# wanco_10V_PSUsch.net
KiCad netlist of a schematic drawn in EAGLE
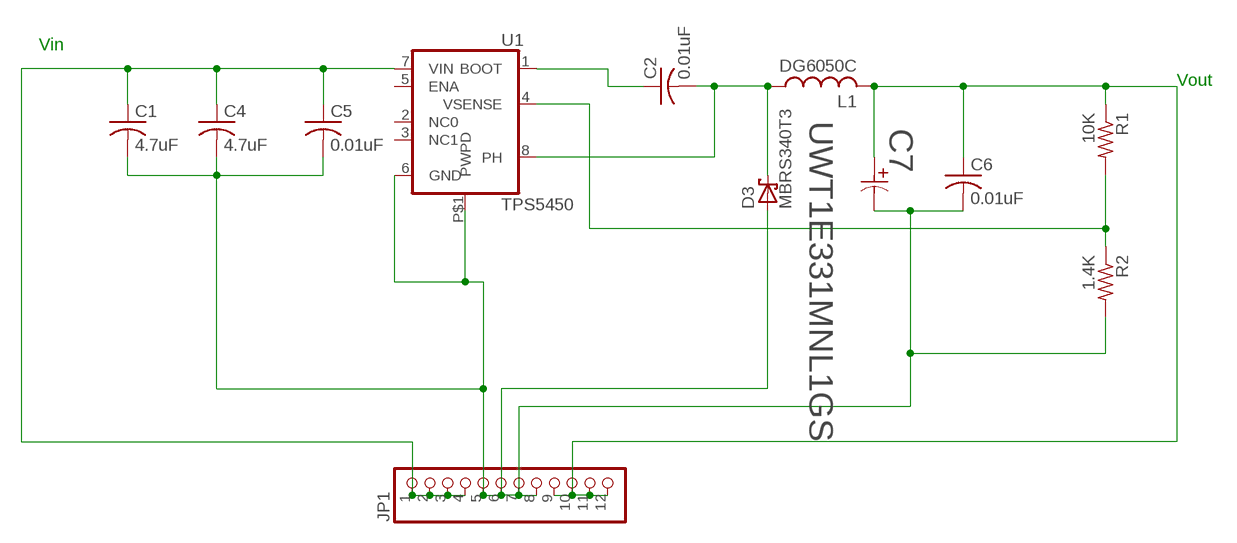
[diagram p0: schematic, sheet 1]

(export (version "E")
  (design (tool "Eeschema 10.0.6"))
  (components
    (comp (ref "C1")
      (value "4.7uF")
      (footprint "eagle-import:C1206")
      (libsource (lib "eagle-import") (part "C-USC1206"))
    )
    (comp (ref "C2")
      (value "0.01uF")
      (footprint "eagle-import:C0805")
      (libsource (lib "eagle-import") (part "resistor_C-USC0805"))
    )
    (comp (ref "C4")
      (value "4.7uF")
      (footprint "eagle-import:C1206")
      (libsource (lib "eagle-import") (part "C-USC1206"))
    )
    (comp (ref "C5")
      (value "0.01uF")
      (footprint "eagle-import:C0805")
      (libsource (lib "eagle-import") (part "resistor_C-USC0805"))
    )
    (comp (ref "C6")
      (value "0.01uF")
      (footprint "eagle-import:C0805")
      (libsource (lib "eagle-import") (part "resistor_C-USC0805"))
    )
    (comp (ref "C7")
      (value "UWT1E331MNL1GS")
      (footprint "eagle-import:PCAP_8X10-ELECT")
      (fields (field (name "COPYRIGHT") "Copyright (C) 2015 Accelerated Designs. All rights reserved"))
      (libsource (lib "eagle-import") (part "UWT1E331MNL1GS"))
    )
    (comp (ref "D3")
      (value "MBRS340T3")
      (footprint "eagle-import:SMC")
      (libsource (lib "eagle-import") (part "MBRS30T34"))
    )
    (comp (ref "JP1")
      (value "PINHD-1X12")
      (footprint "eagle-import:1X12")
      (libsource (lib "eagle-import") (part "PINHD-1X12"))
    )
    (comp (ref "L1")
      (value "DG6050C")
      (footprint "eagle-import:DG")
      (libsource (lib "eagle-import") (part "DG6050C"))
    )
    (comp (ref "R1")
      (value "10K")
      (footprint "eagle-import:R0805")
      (libsource (lib "eagle-import") (part "R-US_R0805"))
    )
    (comp (ref "R2")
      (value "1.4K")
      (footprint "eagle-import:R0805")
      (libsource (lib "eagle-import") (part "R-US_R0805"))
    )
    (comp (ref "U1")
      (value "TPS5450")
      (footprint "eagle-import:SO08")
      (libsource (lib "eagle-import") (part "TPS5450"))
    )
  )
  (nets
    (net (code "1") (name "Net-(C7-11)") (class "Default")
      (node (ref "C6") (pin "1") (pinfunction "1_1") (pintype "passive"))
      (node (ref "C7") (pin "1") (pinfunction "11_1") (pintype "passive"))
      (node (ref "JP1") (pin "10") (pinfunction "10_10") (pintype "passive"))
      (node (ref "JP1") (pin "11") (pinfunction "11_11") (pintype "passive"))
      (node (ref "JP1") (pin "12") (pinfunction "12_12") (pintype "passive"))
      (node (ref "JP1") (pin "9") (pinfunction "9_9") (pintype "passive"))
      (node (ref "L1") (pin "P$2") (pinfunction "2_P$2") (pintype "passive"))
      (node (ref "R1") (pin "1") (pinfunction "1_1") (pintype "passive"))
    )
    (net (code "2") (name "Net-(C7-22)") (class "Default")
      (node (ref "C1") (pin "2") (pinfunction "2_2") (pintype "passive"))
      (node (ref "C4") (pin "2") (pinfunction "2_2") (pintype "passive"))
      (node (ref "C5") (pin "2") (pinfunction "2_2") (pintype "passive"))
      (node (ref "C6") (pin "2") (pinfunction "2_2") (pintype "passive"))
      (node (ref "C7") (pin "2") (pinfunction "22_2") (pintype "passive"))
      (node (ref "D3") (pin "A") (pinfunction "A_A") (pintype "passive"))
      (node (ref "JP1") (pin "5") (pinfunction "5_5") (pintype "passive"))
      (node (ref "JP1") (pin "6") (pinfunction "6_6") (pintype "passive"))
      (node (ref "JP1") (pin "7") (pinfunction "7_7") (pintype "passive"))
      (node (ref "JP1") (pin "8") (pinfunction "8_8") (pintype "passive"))
      (node (ref "R2") (pin "2") (pinfunction "2_2") (pintype "passive"))
      (node (ref "U1") (pin "6") (pinfunction "GND_6") (pintype "input"))
      (node (ref "U1") (pin "P$1") (pinfunction "PWPD_P$1") (pintype "bidirectional"))
    )
    (net (code "3") (name "Net-(L1-1)") (class "Default")
      (node (ref "C2") (pin "2") (pinfunction "2_2") (pintype "passive"))
      (node (ref "D3") (pin "C") (pinfunction "C_C") (pintype "passive"))
      (node (ref "L1") (pin "P$1") (pinfunction "1_P$1") (pintype "passive"))
      (node (ref "U1") (pin "8") (pinfunction "PH_8") (pintype "input"))
    )
    (net (code "4") (name "Net-(U1-BOOT)") (class "Default")
      (node (ref "C2") (pin "1") (pinfunction "1_1") (pintype "passive"))
      (node (ref "U1") (pin "1") (pinfunction "BOOT_1") (pintype "output"))
    )
    (net (code "5") (name "Net-(U1-VIN)") (class "Default")
      (node (ref "C1") (pin "1") (pinfunction "1_1") (pintype "passive"))
      (node (ref "C4") (pin "1") (pinfunction "1_1") (pintype "passive"))
      (node (ref "C5") (pin "1") (pinfunction "1_1") (pintype "passive"))
      (node (ref "JP1") (pin "1") (pinfunction "1_1") (pintype "passive"))
      (node (ref "JP1") (pin "2") (pinfunction "2_2") (pintype "passive"))
      (node (ref "JP1") (pin "3") (pinfunction "3_3") (pintype "passive"))
      (node (ref "JP1") (pin "4") (pinfunction "4_4") (pintype "passive"))
      (node (ref "U1") (pin "7") (pinfunction "VIN_7") (pintype "input"))
    )
    (net (code "6") (name "Net-(U1-VSENSE)") (class "Default")
      (node (ref "R1") (pin "2") (pinfunction "2_2") (pintype "passive"))
      (node (ref "R2") (pin "1") (pinfunction "1_1") (pintype "passive"))
      (node (ref "U1") (pin "4") (pinfunction "VSENSE_4") (pintype "passive"))
    )
    (net (code "7") (name "unconnected-(U1-ENA-Pad5)") (class "Default")
      (node (ref "U1") (pin "5") (pinfunction "ENA_5") (pintype "input"))
    )
    (net (code "8") (name "unconnected-(U1-NC0-Pad2)") (class "Default")
      (node (ref "U1") (pin "2") (pinfunction "NC0_2") (pintype "input"))
    )
    (net (code "9") (name "unconnected-(U1-NC1-Pad3)") (class "Default")
      (node (ref "U1") (pin "3") (pinfunction "NC1_3") (pintype "input"))
    )
  )
)
